# Pendant.net
KiCad netlist of a schematic drawn in EAGLE
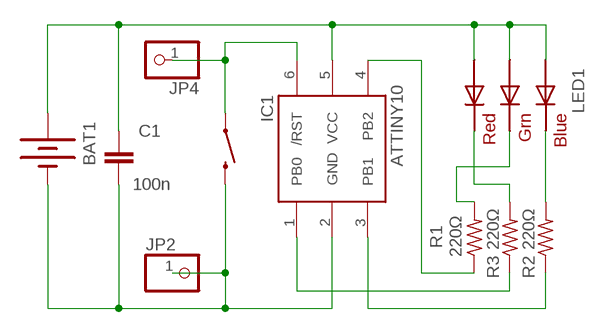
[diagram p0: schematic, sheet 1]

(export (version "E")
  (design (tool "Eeschema 10.0.6"))
  (components
    (comp (ref "BAT1")
      (value "BATTERY12MM")
      (footprint "eagle-import:BATTCON_12MM")
      (libsource (lib "eagle-import") (part "BATTERY12MM"))
    )
    (comp (ref "C1")
      (value "100n")
      (footprint "eagle-import:0603-CAP")
      (libsource (lib "eagle-import") (part "CAP0603-CAP"))
    )
    (comp (ref "IC1")
      (value "ATTINY10")
      (footprint "eagle-import:SOT23-6")
      (libsource (lib "eagle-import") (part "ATTINY10"))
    )
    (comp (ref "JP2")
      (value "PINHD-1X1CB")
      (footprint "eagle-import:1X01-CLEANBIG")
      (libsource (lib "eagle-import") (part "PINHD-1X1CB"))
    )
    (comp (ref "JP4")
      (value "PINHD-1X1CB")
      (footprint "eagle-import:1X01-CLEANBIG")
      (libsource (lib "eagle-import") (part "PINHD-1X1CB"))
    )
    (comp (ref "LED1")
      (value "RGBLED5050")
      (footprint "eagle-import:RGBLED5050")
      (libsource (lib "eagle-import") (part "RGBLED5050"))
    )
    (comp (ref "R1")
      (value "220Ω")
      (footprint "eagle-import:R0805")
      (libsource (lib "eagle-import") (part "R-US_R0805"))
    )
    (comp (ref "R2")
      (value "220Ω")
      (footprint "eagle-import:R0805")
      (libsource (lib "eagle-import") (part "R-US_R0805"))
    )
    (comp (ref "R3")
      (value "220Ω")
      (footprint "eagle-import:R0805")
      (libsource (lib "eagle-import") (part "R-US_R0805"))
    )
    (comp (ref "S2")
      (value "SWITCH-MOMENTARY-2SMD")
      (footprint "eagle-import:TACTILE-SWITCH-SMD")
      (libsource (lib "eagle-import") (part "SWITCH-MOMENTARY-2SMD"))
    )
  )
  (nets
    (net (code "1") (name "Net-(BAT1-+)") (class "Default")
      (node (ref "BAT1") (pin "PWR@1") (pinfunction "+_PWR@1") (pintype "power_in"))
      (node (ref "C1") (pin "1") (pinfunction "1_1") (pintype "passive"))
      (node (ref "IC1") (pin "5") (pinfunction "VCC_5") (pintype "power_in"))
      (node (ref "LED1") (pin "1") (pinfunction "GREEN_A_1") (pintype "bidirectional"))
      (node (ref "LED1") (pin "2") (pinfunction "RED_A_2") (pintype "bidirectional"))
      (node (ref "LED1") (pin "3") (pinfunction "BLUE_A_3") (pintype "bidirectional"))
    )
    (net (code "2") (name "Net-(BAT1--)") (class "Default")
      (node (ref "BAT1") (pin "GND") (pinfunction "-_GND") (pintype "power_in"))
      (node (ref "C1") (pin "2") (pinfunction "2_2") (pintype "passive"))
      (node (ref "IC1") (pin "2") (pinfunction "GND_2") (pintype "power_in"))
      (node (ref "JP2") (pin "1") (pinfunction "1_1") (pintype "passive"))
      (node (ref "S2") (pin "3") (pinfunction "2_3") (pintype "passive"))
    )
    (net (code "3") (name "Net-(IC1-PB0)") (class "Default")
      (node (ref "IC1") (pin "1") (pinfunction "PB0_1") (pintype "bidirectional"))
      (node (ref "R3") (pin "1") (pinfunction "1_1") (pintype "passive"))
    )
    (net (code "4") (name "Net-(IC1-PB1)") (class "Default")
      (node (ref "IC1") (pin "3") (pinfunction "PB1_3") (pintype "bidirectional"))
      (node (ref "R2") (pin "1") (pinfunction "1_1") (pintype "passive"))
    )
    (net (code "5") (name "Net-(IC1-PB2)") (class "Default")
      (node (ref "IC1") (pin "4") (pinfunction "PB2_4") (pintype "bidirectional"))
      (node (ref "R1") (pin "1") (pinfunction "1_1") (pintype "passive"))
    )
    (net (code "6") (name "Net-(IC1-{slash}RST)") (class "Default")
      (node (ref "IC1") (pin "6") (pinfunction "/RST_6") (pintype "bidirectional"))
      (node (ref "JP4") (pin "1") (pinfunction "1_1") (pintype "passive"))
      (node (ref "S2") (pin "1") (pinfunction "1_1") (pintype "passive"))
    )
    (net (code "7") (name "Net-(LED1-BLUE_C)") (class "Default")
      (node (ref "LED1") (pin "4") (pinfunction "BLUE_C_4") (pintype "bidirectional"))
      (node (ref "R2") (pin "2") (pinfunction "2_2") (pintype "passive"))
    )
    (net (code "8") (name "Net-(LED1-GREEN_C)") (class "Default")
      (node (ref "LED1") (pin "6") (pinfunction "GREEN_C_6") (pintype "bidirectional"))
      (node (ref "R1") (pin "2") (pinfunction "2_2") (pintype "passive"))
    )
    (net (code "9") (name "Net-(LED1-RED_C)") (class "Default")
      (node (ref "LED1") (pin "5") (pinfunction "RED_C_5") (pintype "bidirectional"))
      (node (ref "R3") (pin "2") (pinfunction "2_2") (pintype "passive"))
    )
  )
)
